# Joystick.net
KiCad netlist of a schematic drawn in EAGLE
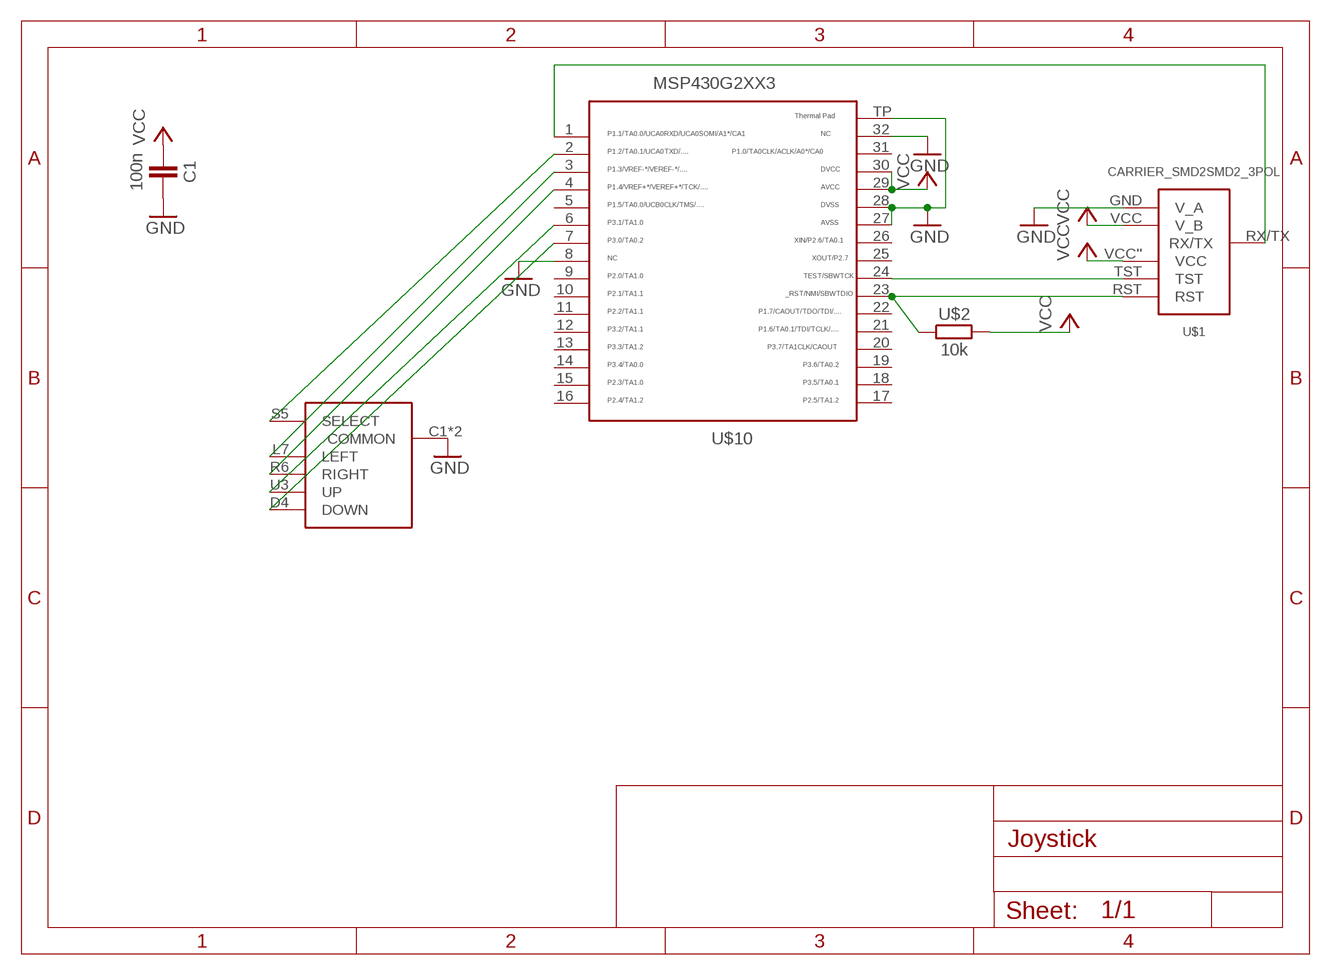
[diagram p0: schematic, sheet 1]

(export (version "E")
  (design (tool "Eeschema 10.0.6"))
  (components
    (comp (ref "C1")
      (value "100n")
      (footprint "eagle-import:603")
      (libsource (lib "eagle-import") (part "CAPACITOR"))
    )
    (comp (ref "U$1")
      (value "CARRIER_SMD2SMD2_3POL")
      (footprint "eagle-import:CARRIER_SMD2_3POL")
      (libsource (lib "eagle-import") (part "CARRIER_SMD2SMD2_3POL"))
    )
    (comp (ref "U$2")
      (value "10k")
      (footprint "eagle-import:603")
      (libsource (lib "eagle-import") (part "RESISTOR0603"))
    )
    (comp (ref "U$3")
      (value "JOYSTICK")
      (footprint "eagle-import:JOYSTICK")
      (libsource (lib "eagle-import") (part "JOYSTICK"))
    )
    (comp (ref "U$10")
      (value "MSP430G2553")
      (footprint "eagle-import:QFN32")
      (libsource (lib "eagle-import") (part "MSP430G2553"))
    )
  )
  (nets
    (net (code "1") (name "GND") (class "Default")
      (node (ref "C1") (pin "2") (pinfunction "2_2") (pintype "passive"))
      (node (ref "U$1") (pin "GND") (pinfunction "V_A_GND") (pintype "bidirectional"))
      (node (ref "U$10") (pin "27") (pinfunction "27_27") (pintype "bidirectional"))
      (node (ref "U$10") (pin "28") (pinfunction "28_28") (pintype "bidirectional"))
      (node (ref "U$10") (pin "32") (pinfunction "32_32") (pintype "bidirectional"))
      (node (ref "U$10") (pin "8") (pinfunction "8_8") (pintype "bidirectional"))
      (node (ref "U$10") (pin "TP") (pinfunction "TP_TP") (pintype "bidirectional"))
      (node (ref "U$3") (pin "C1") (pinfunction "COMMON_C1") (pintype "bidirectional"))
      (node (ref "U$3") (pin "C2") (pinfunction "COMMON_C2") (pintype "bidirectional"))
    )
    (net (code "2") (name "Net-(U$1-PadRST)") (class "Default")
      (node (ref "U$1") (pin "RST") (pinfunction "RST_RST") (pintype "bidirectional"))
      (node (ref "U$10") (pin "23") (pinfunction "23_23") (pintype "bidirectional"))
      (node (ref "U$2") (pin "1") (pinfunction "1_1") (pintype "passive"))
    )
    (net (code "3") (name "Net-(U$1-PadRX{slash}TX)") (class "Default")
      (node (ref "U$1") (pin "RX/TX") (pinfunction "RX/TX_RX/TX") (pintype "bidirectional"))
      (node (ref "U$10") (pin "1") (pinfunction "1_1") (pintype "bidirectional"))
    )
    (net (code "4") (name "Net-(U$1-PadTST)") (class "Default")
      (node (ref "U$1") (pin "TST") (pinfunction "TST_TST") (pintype "bidirectional"))
      (node (ref "U$10") (pin "24") (pinfunction "24_24") (pintype "bidirectional"))
    )
    (net (code "5") (name "Net-(U$3-DOWN)") (class "Default")
      (node (ref "U$10") (pin "7") (pinfunction "7_7") (pintype "bidirectional"))
      (node (ref "U$3") (pin "D4") (pinfunction "DOWN_D4") (pintype "bidirectional"))
    )
    (net (code "6") (name "Net-(U$3-LEFT)") (class "Default")
      (node (ref "U$10") (pin "3") (pinfunction "3_3") (pintype "bidirectional"))
      (node (ref "U$3") (pin "L7") (pinfunction "LEFT_L7") (pintype "bidirectional"))
    )
    (net (code "7") (name "Net-(U$3-RIGHT)") (class "Default")
      (node (ref "U$10") (pin "4") (pinfunction "4_4") (pintype "bidirectional"))
      (node (ref "U$3") (pin "R6") (pinfunction "RIGHT_R6") (pintype "bidirectional"))
    )
    (net (code "8") (name "Net-(U$3-SELECT)") (class "Default")
      (node (ref "U$10") (pin "2") (pinfunction "2_2") (pintype "bidirectional"))
      (node (ref "U$3") (pin "S5") (pinfunction "SELECT_S5") (pintype "bidirectional"))
    )
    (net (code "9") (name "Net-(U$3-UP)") (class "Default")
      (node (ref "U$10") (pin "6") (pinfunction "6_6") (pintype "bidirectional"))
      (node (ref "U$3") (pin "U3") (pinfunction "UP_U3") (pintype "bidirectional"))
    )
    (net (code "10") (name "VCC") (class "Default")
      (node (ref "C1") (pin "1") (pinfunction "1_1") (pintype "passive"))
      (node (ref "U$1") (pin "VCC") (pinfunction "V_B_VCC") (pintype "bidirectional"))
      (node (ref "U$1") (pin "VCC''") (pinfunction "VCC_VCC''") (pintype "bidirectional"))
      (node (ref "U$10") (pin "29") (pinfunction "29_29") (pintype "bidirectional"))
      (node (ref "U$10") (pin "30") (pinfunction "30_30") (pintype "bidirectional"))
      (node (ref "U$2") (pin "2") (pinfunction "2_2") (pintype "passive"))
    )
    (net (code "11") (name "unconnected-(U$10-Pad5)") (class "Default")
      (node (ref "U$10") (pin "5") (pinfunction "5_5") (pintype "bidirectional"))
    )
    (net (code "12") (name "unconnected-(U$10-Pad9)") (class "Default")
      (node (ref "U$10") (pin "9") (pinfunction "9_9") (pintype "bidirectional"))
    )
    (net (code "13") (name "unconnected-(U$10-Pad10)") (class "Default")
      (node (ref "U$10") (pin "10") (pinfunction "10_10") (pintype "bidirectional"))
    )
    (net (code "14") (name "unconnected-(U$10-Pad11)") (class "Default")
      (node (ref "U$10") (pin "11") (pinfunction "11_11") (pintype "bidirectional"))
    )
    (net (code "15") (name "unconnected-(U$10-Pad12)") (class "Default")
      (node (ref "U$10") (pin "12") (pinfunction "12_12") (pintype "bidirectional"))
    )
    (net (code "16") (name "unconnected-(U$10-Pad13)") (class "Default")
      (node (ref "U$10") (pin "13") (pinfunction "13_13") (pintype "bidirectional"))
    )
    (net (code "17") (name "unconnected-(U$10-Pad14)") (class "Default")
      (node (ref "U$10") (pin "14") (pinfunction "14_14") (pintype "bidirectional"))
    )
    (net (code "18") (name "unconnected-(U$10-Pad15)") (class "Default")
      (node (ref "U$10") (pin "15") (pinfunction "15_15") (pintype "bidirectional"))
    )
    (net (code "19") (name "unconnected-(U$10-Pad16)") (class "Default")
      (node (ref "U$10") (pin "16") (pinfunction "16_16") (pintype "bidirectional"))
    )
    (net (code "20") (name "unconnected-(U$10-Pad17)") (class "Default")
      (node (ref "U$10") (pin "17") (pinfunction "17_17") (pintype "bidirectional"))
    )
    (net (code "21") (name "unconnected-(U$10-Pad18)") (class "Default")
      (node (ref "U$10") (pin "18") (pinfunction "18_18") (pintype "bidirectional"))
    )
    (net (code "22") (name "unconnected-(U$10-Pad19)") (class "Default")
      (node (ref "U$10") (pin "19") (pinfunction "19_19") (pintype "bidirectional"))
    )
    (net (code "23") (name "unconnected-(U$10-Pad20)") (class "Default")
      (node (ref "U$10") (pin "20") (pinfunction "20_20") (pintype "bidirectional"))
    )
    (net (code "24") (name "unconnected-(U$10-Pad21)") (class "Default")
      (node (ref "U$10") (pin "21") (pinfunction "21_21") (pintype "bidirectional"))
    )
    (net (code "25") (name "unconnected-(U$10-Pad22)") (class "Default")
      (node (ref "U$10") (pin "22") (pinfunction "22_22") (pintype "bidirectional"))
    )
    (net (code "26") (name "unconnected-(U$10-Pad25)") (class "Default")
      (node (ref "U$10") (pin "25") (pinfunction "25_25") (pintype "bidirectional"))
    )
    (net (code "27") (name "unconnected-(U$10-Pad26)") (class "Default")
      (node (ref "U$10") (pin "26") (pinfunction "26_26") (pintype "bidirectional"))
    )
    (net (code "28") (name "unconnected-(U$10-Pad31)") (class "Default")
      (node (ref "U$10") (pin "31") (pinfunction "31_31") (pintype "bidirectional"))
    )
  )
)
